# frankShield.net
KiCad netlist of a schematic drawn in EAGLE
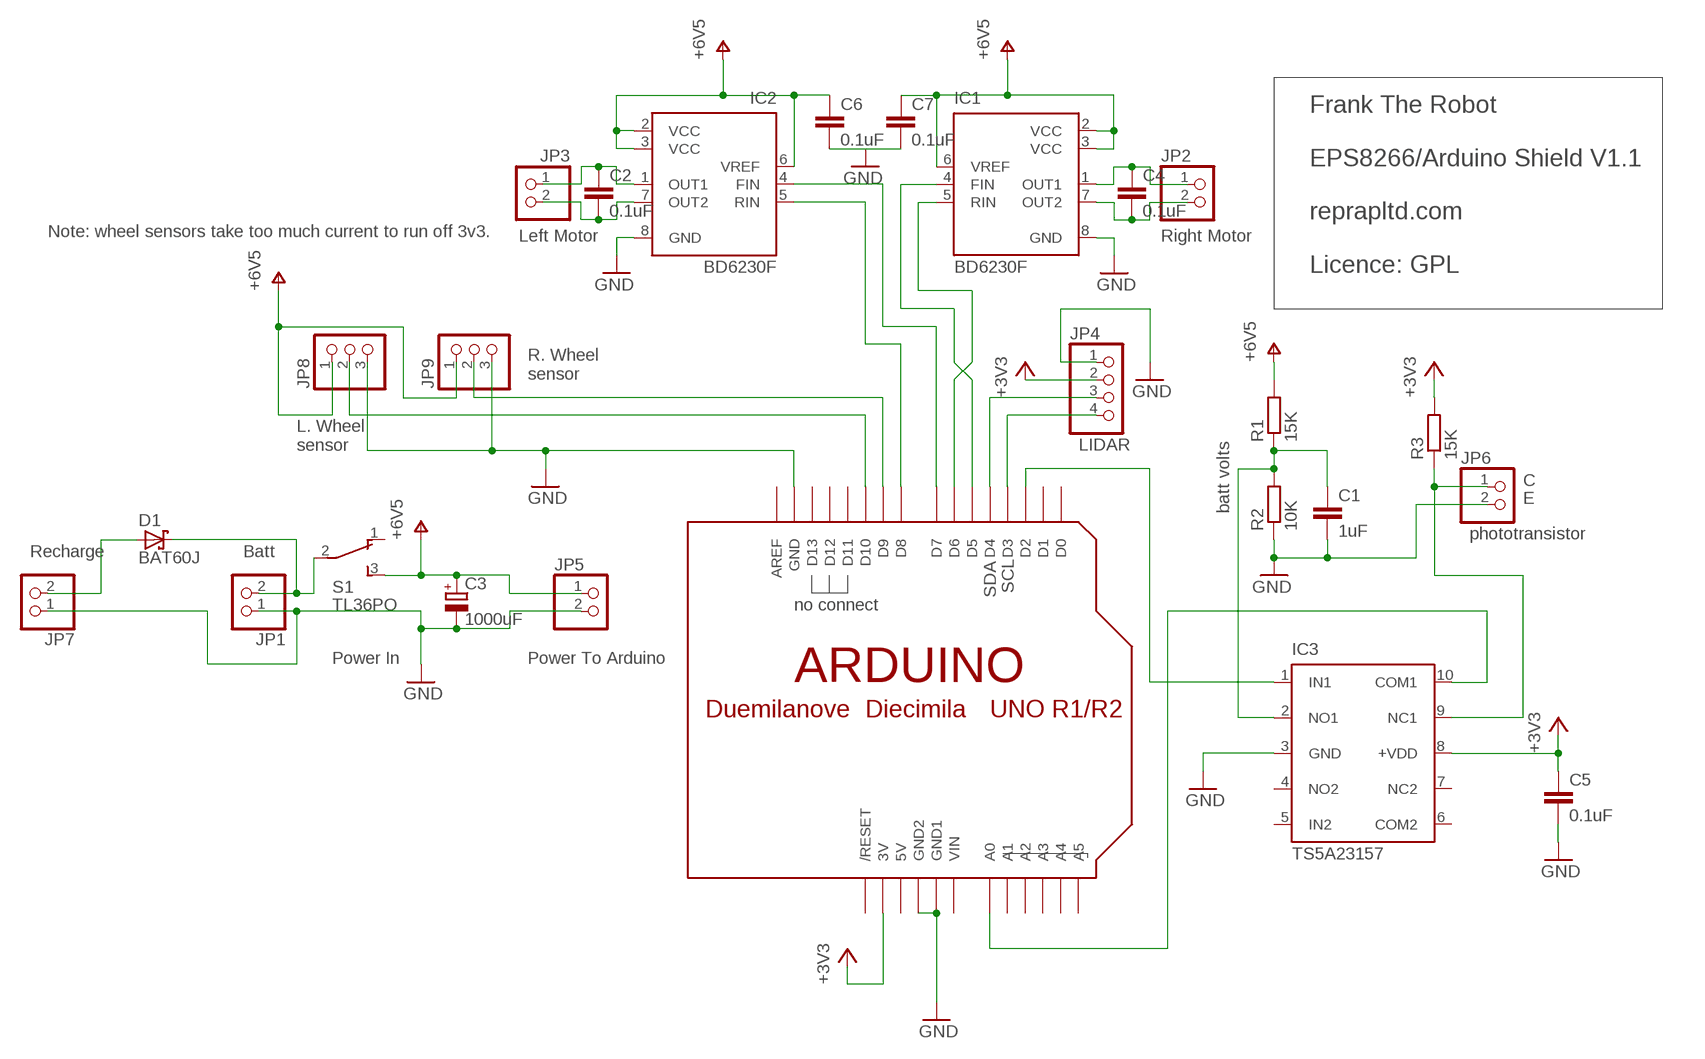
[diagram p0: schematic, sheet 1]

(export (version "E")
  (design (tool "Eeschema 10.0.6"))
  (components
    (comp (ref "C1")
      (value "1uF")
      (footprint "eagle-import:C0805")
      (libsource (lib "eagle-import") (part "C-EUC0805"))
    )
    (comp (ref "C2")
      (value "0.1uF")
      (footprint "eagle-import:C0805")
      (libsource (lib "eagle-import") (part "C-EUC0805"))
    )
    (comp (ref "C3")
      (value "1000uF")
      (footprint "eagle-import:B45181B")
      (libsource (lib "eagle-import") (part "CPOL-EUB45181B"))
    )
    (comp (ref "C4")
      (value "0.1uF")
      (footprint "eagle-import:C0805")
      (libsource (lib "eagle-import") (part "C-EUC0805"))
    )
    (comp (ref "C5")
      (value "0.1uF")
      (footprint "eagle-import:C0805")
      (libsource (lib "eagle-import") (part "C-EUC0805"))
    )
    (comp (ref "C6")
      (value "0.1uF")
      (footprint "eagle-import:C0805")
      (libsource (lib "eagle-import") (part "C-EUC0805"))
    )
    (comp (ref "C7")
      (value "0.1uF")
      (footprint "eagle-import:C0805")
      (libsource (lib "eagle-import") (part "C-EUC0805"))
    )
    (comp (ref "D1")
      (value "BAT60J")
      (footprint "eagle-import:SOD323_ST")
      (libsource (lib "eagle-import") (part "BAT60J"))
    )
    (comp (ref "IC1")
      (value "BD6230F")
      (footprint "eagle-import:SOP8")
      (fields (field (name "MPN") "BD6230F-E2"))
      (libsource (lib "eagle-import") (part "BD623F0"))
    )
    (comp (ref "IC2")
      (value "BD6230F")
      (footprint "eagle-import:SOP8")
      (fields (field (name "MPN") "BD6230F-E2"))
      (libsource (lib "eagle-import") (part "BD623F0"))
    )
    (comp (ref "IC3")
      (value "TS5A23157")
      (footprint "eagle-import:MSOP10")
      (fields (field (name "MPN") "AD7992BRMZ-0"))
      (libsource (lib "eagle-import") (part "TS5A23157"))
    )
    (comp (ref "JP1")
      (value "PINHD-1X2")
      (footprint "eagle-import:1X02")
      (libsource (lib "eagle-import") (part "PINHD-1X2"))
    )
    (comp (ref "JP2")
      (value "PINHD-1X2")
      (footprint "eagle-import:1X02")
      (libsource (lib "eagle-import") (part "PINHD-1X2"))
    )
    (comp (ref "JP3")
      (value "PINHD-1X2")
      (footprint "eagle-import:1X02")
      (libsource (lib "eagle-import") (part "PINHD-1X2"))
    )
    (comp (ref "JP4")
      (value "PINHD-1X4")
      (footprint "eagle-import:1X04")
      (libsource (lib "eagle-import") (part "PINHD-1X4"))
    )
    (comp (ref "JP5")
      (value "PINHD-1X2")
      (footprint "eagle-import:1X02")
      (libsource (lib "eagle-import") (part "PINHD-1X2"))
    )
    (comp (ref "JP6")
      (value "PINHD-1X2")
      (footprint "eagle-import:1X02")
      (libsource (lib "eagle-import") (part "PINHD-1X2"))
    )
    (comp (ref "JP7")
      (value "PINHD-1X2")
      (footprint "eagle-import:1X02")
      (libsource (lib "eagle-import") (part "PINHD-1X2"))
    )
    (comp (ref "JP8")
      (value "PINHD-1X3")
      (footprint "eagle-import:1X03")
      (libsource (lib "eagle-import") (part "PINHD-1X3"))
    )
    (comp (ref "JP9")
      (value "PINHD-1X3")
      (footprint "eagle-import:1X03")
      (libsource (lib "eagle-import") (part "PINHD-1X3"))
    )
    (comp (ref "R1")
      (value "15K")
      (footprint "eagle-import:M0805")
      (libsource (lib "eagle-import") (part "R-EU_M0805"))
    )
    (comp (ref "R2")
      (value "10K")
      (footprint "eagle-import:M0805")
      (libsource (lib "eagle-import") (part "R-EU_M0805"))
    )
    (comp (ref "R3")
      (value "15K")
      (footprint "eagle-import:M0805")
      (libsource (lib "eagle-import") (part "R-EU_M0805"))
    )
    (comp (ref "S1")
      (value "TL36PO")
      (footprint "eagle-import:TL3XPO")
      (libsource (lib "eagle-import") (part "TL36PO"))
    )
    (comp (ref "U$1")
      (value "ARDUINO-BPLACE")
      (footprint "eagle-import:ARDUINO-BPLACE")
      (libsource (lib "eagle-import") (part "ARDUINO-BPLACE"))
    )
  )
  (nets
    (net (code "1") (name "+3V3") (class "Default")
      (node (ref "C5") (pin "1") (pinfunction "1_1") (pintype "passive"))
      (node (ref "IC3") (pin "8") (pinfunction "+VDD_8") (pintype "output"))
      (node (ref "JP4") (pin "2") (pinfunction "2_2") (pintype "passive"))
      (node (ref "R3") (pin "2") (pinfunction "2_2") (pintype "passive"))
      (node (ref "U$1") (pin "3V") (pinfunction "3V_3V") (pintype "power_in"))
    )
    (net (code "2") (name "+6V5") (class "Default")
      (node (ref "C3") (pin "+") (pinfunction "+_+") (pintype "passive"))
      (node (ref "C6") (pin "1") (pinfunction "1_1") (pintype "passive"))
      (node (ref "C7") (pin "1") (pinfunction "1_1") (pintype "passive"))
      (node (ref "IC1") (pin "2") (pinfunction "VCC_2") (pintype "power_in"))
      (node (ref "IC1") (pin "3") (pinfunction "VCC_3") (pintype "power_in"))
      (node (ref "IC1") (pin "6") (pinfunction "VREF_6") (pintype "passive"))
      (node (ref "IC2") (pin "2") (pinfunction "VCC_2") (pintype "power_in"))
      (node (ref "IC2") (pin "3") (pinfunction "VCC_3") (pintype "power_in"))
      (node (ref "IC2") (pin "6") (pinfunction "VREF_6") (pintype "passive"))
      (node (ref "JP5") (pin "1") (pinfunction "1_1") (pintype "passive"))
      (node (ref "JP8") (pin "1") (pinfunction "1_1") (pintype "passive"))
      (node (ref "JP9") (pin "1") (pinfunction "1_1") (pintype "passive"))
      (node (ref "R1") (pin "2") (pinfunction "2_2") (pintype "passive"))
      (node (ref "S1") (pin "3") (pinfunction "S_3") (pintype "passive"))
    )
    (net (code "3") (name "/5V") (class "Default")
      (node (ref "U$1") (pin "5V") (pinfunction "5V_5V") (pintype "power_in"))
    )
    (net (code "4") (name "/NC2") (class "Default")
      (node (ref "IC3") (pin "7") (pinfunction "NC2_7") (pintype "power_in"))
    )
    (net (code "5") (name "/VIN") (class "Default")
      (node (ref "U$1") (pin "VIN") (pinfunction "VIN_VIN") (pintype "power_in"))
    )
    (net (code "6") (name "GND") (class "Default")
      (node (ref "C1") (pin "2") (pinfunction "2_2") (pintype "passive"))
      (node (ref "C3") (pin "-") (pinfunction "-_-") (pintype "passive"))
      (node (ref "C5") (pin "2") (pinfunction "2_2") (pintype "passive"))
      (node (ref "C6") (pin "2") (pinfunction "2_2") (pintype "passive"))
      (node (ref "C7") (pin "2") (pinfunction "2_2") (pintype "passive"))
      (node (ref "IC1") (pin "8") (pinfunction "GND_8") (pintype "power_in"))
      (node (ref "IC2") (pin "8") (pinfunction "GND_8") (pintype "power_in"))
      (node (ref "IC3") (pin "3") (pinfunction "GND_3") (pintype "power_in"))
      (node (ref "JP1") (pin "1") (pinfunction "1_1") (pintype "passive"))
      (node (ref "JP4") (pin "1") (pinfunction "1_1") (pintype "passive"))
      (node (ref "JP5") (pin "2") (pinfunction "2_2") (pintype "passive"))
      (node (ref "JP6") (pin "2") (pinfunction "2_2") (pintype "passive"))
      (node (ref "JP7") (pin "1") (pinfunction "1_1") (pintype "passive"))
      (node (ref "JP8") (pin "3") (pinfunction "3_3") (pintype "passive"))
      (node (ref "JP9") (pin "3") (pinfunction "3_3") (pintype "passive"))
      (node (ref "R2") (pin "1") (pinfunction "1_1") (pintype "passive"))
      (node (ref "U$1") (pin "GND") (pinfunction "GND_GND") (pintype "power_in"))
      (node (ref "U$1") (pin "GND1") (pinfunction "GND1_GND1") (pintype "power_in"))
      (node (ref "U$1") (pin "GND2") (pinfunction "GND2_GND2") (pintype "power_in"))
    )
    (net (code "7") (name "Net-(D1-PadA)") (class "Default")
      (node (ref "D1") (pin "A") (pinfunction "A_A") (pintype "passive"))
      (node (ref "JP7") (pin "2") (pinfunction "2_2") (pintype "passive"))
    )
    (net (code "8") (name "Net-(IC1-FIN)") (class "Default")
      (node (ref "IC1") (pin "4") (pinfunction "FIN_4") (pintype "input"))
      (node (ref "U$1") (pin "D5") (pinfunction "D5_D5") (pintype "bidirectional"))
    )
    (net (code "9") (name "Net-(IC1-OUT1)") (class "Default")
      (node (ref "C4") (pin "1") (pinfunction "1_1") (pintype "passive"))
      (node (ref "IC1") (pin "1") (pinfunction "OUT1_1") (pintype "output"))
      (node (ref "JP2") (pin "1") (pinfunction "1_1") (pintype "passive"))
    )
    (net (code "10") (name "Net-(IC1-OUT2)") (class "Default")
      (node (ref "C4") (pin "2") (pinfunction "2_2") (pintype "passive"))
      (node (ref "IC1") (pin "7") (pinfunction "OUT2_7") (pintype "output"))
      (node (ref "JP2") (pin "2") (pinfunction "2_2") (pintype "passive"))
    )
    (net (code "11") (name "Net-(IC1-RIN)") (class "Default")
      (node (ref "IC1") (pin "5") (pinfunction "RIN_5") (pintype "input"))
      (node (ref "U$1") (pin "D6") (pinfunction "D6_D6") (pintype "bidirectional"))
    )
    (net (code "12") (name "Net-(IC2-FIN)") (class "Default")
      (node (ref "IC2") (pin "4") (pinfunction "FIN_4") (pintype "input"))
      (node (ref "U$1") (pin "D7") (pinfunction "D7_D7") (pintype "bidirectional"))
    )
    (net (code "13") (name "Net-(IC2-OUT1)") (class "Default")
      (node (ref "C2") (pin "1") (pinfunction "1_1") (pintype "passive"))
      (node (ref "IC2") (pin "1") (pinfunction "OUT1_1") (pintype "output"))
      (node (ref "JP3") (pin "1") (pinfunction "1_1") (pintype "passive"))
    )
    (net (code "14") (name "Net-(IC2-OUT2)") (class "Default")
      (node (ref "C2") (pin "2") (pinfunction "2_2") (pintype "passive"))
      (node (ref "IC2") (pin "7") (pinfunction "OUT2_7") (pintype "output"))
      (node (ref "JP3") (pin "2") (pinfunction "2_2") (pintype "passive"))
    )
    (net (code "15") (name "Net-(IC2-RIN)") (class "Default")
      (node (ref "IC2") (pin "5") (pinfunction "RIN_5") (pintype "input"))
      (node (ref "U$1") (pin "D8") (pinfunction "D8_D8") (pintype "bidirectional"))
    )
    (net (code "16") (name "Net-(IC3-COM1)") (class "Default")
      (node (ref "IC3") (pin "10") (pinfunction "COM1_10") (pintype "input"))
      (node (ref "U$1") (pin "A0") (pinfunction "A0_A0") (pintype "bidirectional"))
    )
    (net (code "17") (name "Net-(IC3-IN1)") (class "Default")
      (node (ref "IC3") (pin "1") (pinfunction "IN1_1") (pintype "input"))
      (node (ref "U$1") (pin "D2") (pinfunction "D2_D2") (pintype "bidirectional"))
    )
    (net (code "18") (name "Net-(IC3-NC1)") (class "Default")
      (node (ref "IC3") (pin "9") (pinfunction "NC1_9") (pintype "bidirectional"))
      (node (ref "JP6") (pin "1") (pinfunction "1_1") (pintype "passive"))
      (node (ref "R3") (pin "1") (pinfunction "1_1") (pintype "passive"))
    )
    (net (code "19") (name "Net-(IC3-NO1)") (class "Default")
      (node (ref "C1") (pin "1") (pinfunction "1_1") (pintype "passive"))
      (node (ref "IC3") (pin "2") (pinfunction "NO1_2") (pintype "power_in"))
      (node (ref "R1") (pin "1") (pinfunction "1_1") (pintype "passive"))
      (node (ref "R2") (pin "2") (pinfunction "2_2") (pintype "passive"))
    )
    (net (code "20") (name "Net-(JP4-Pad3)") (class "Default")
      (node (ref "JP4") (pin "3") (pinfunction "3_3") (pintype "passive"))
      (node (ref "U$1") (pin "D4") (pinfunction "D4_D4") (pintype "bidirectional"))
    )
    (net (code "21") (name "Net-(JP4-Pad4)") (class "Default")
      (node (ref "JP4") (pin "4") (pinfunction "4_4") (pintype "passive"))
      (node (ref "U$1") (pin "D3") (pinfunction "D3_D3") (pintype "bidirectional"))
    )
    (net (code "22") (name "Net-(JP8-Pad2)") (class "Default")
      (node (ref "JP8") (pin "2") (pinfunction "2_2") (pintype "passive"))
      (node (ref "U$1") (pin "D10") (pinfunction "D10_D10") (pintype "bidirectional"))
    )
    (net (code "23") (name "Net-(JP9-Pad2)") (class "Default")
      (node (ref "JP9") (pin "2") (pinfunction "2_2") (pintype "passive"))
      (node (ref "U$1") (pin "D9") (pinfunction "D9_D9") (pintype "bidirectional"))
    )
    (net (code "24") (name "Net-(S1-P)") (class "Default")
      (node (ref "D1") (pin "C") (pinfunction "C_C") (pintype "passive"))
      (node (ref "JP1") (pin "2") (pinfunction "2_2") (pintype "passive"))
      (node (ref "S1") (pin "2") (pinfunction "P_2") (pintype "passive"))
    )
    (net (code "25") (name "unconnected-(IC3-COM2-Pad6)") (class "Default")
      (node (ref "IC3") (pin "6") (pinfunction "COM2_6") (pintype "input"))
    )
    (net (code "26") (name "unconnected-(IC3-IN2-Pad5)") (class "Default")
      (node (ref "IC3") (pin "5") (pinfunction "IN2_5") (pintype "input"))
    )
    (net (code "27") (name "unconnected-(IC3-NO2-Pad4)") (class "Default")
      (node (ref "IC3") (pin "4") (pinfunction "NO2_4") (pintype "input"))
    )
    (net (code "28") (name "unconnected-(S1-O-Pad1)") (class "Default")
      (node (ref "S1") (pin "1") (pinfunction "O_1") (pintype "passive"))
    )
    (net (code "29") (name "unconnected-(U$1-PadA1)") (class "Default")
      (node (ref "U$1") (pin "A1") (pinfunction "A1_A1") (pintype "bidirectional"))
    )
    (net (code "30") (name "unconnected-(U$1-PadA2)") (class "Default")
      (node (ref "U$1") (pin "A2") (pinfunction "A2_A2") (pintype "bidirectional"))
    )
    (net (code "31") (name "unconnected-(U$1-PadA3)") (class "Default")
      (node (ref "U$1") (pin "A3") (pinfunction "A3_A3") (pintype "bidirectional"))
    )
    (net (code "32") (name "unconnected-(U$1-PadA4)") (class "Default")
      (node (ref "U$1") (pin "A4") (pinfunction "A4_A4") (pintype "bidirectional"))
    )
    (net (code "33") (name "unconnected-(U$1-PadA5)") (class "Default")
      (node (ref "U$1") (pin "A5") (pinfunction "A5_A5") (pintype "bidirectional"))
    )
    (net (code "34") (name "unconnected-(U$1-PadAREF)") (class "Default")
      (node (ref "U$1") (pin "AREF") (pinfunction "AREF_AREF") (pintype "bidirectional"))
    )
    (net (code "35") (name "unconnected-(U$1-PadD0)") (class "Default")
      (node (ref "U$1") (pin "D0") (pinfunction "D0_D0") (pintype "bidirectional"))
    )
    (net (code "36") (name "unconnected-(U$1-PadD1)") (class "Default")
      (node (ref "U$1") (pin "D1") (pinfunction "D1_D1") (pintype "bidirectional"))
    )
    (net (code "37") (name "unconnected-(U$1-PadD11)") (class "Default")
      (node (ref "U$1") (pin "D11") (pinfunction "D11_D11") (pintype "bidirectional"))
    )
    (net (code "38") (name "unconnected-(U$1-PadD12)") (class "Default")
      (node (ref "U$1") (pin "D12") (pinfunction "D12_D12") (pintype "bidirectional"))
    )
    (net (code "39") (name "unconnected-(U$1-PadD13)") (class "Default")
      (node (ref "U$1") (pin "D13") (pinfunction "D13_D13") (pintype "bidirectional"))
    )
    (net (code "40") (name "unconnected-(U$1-{slash}RESET-PadRESET)") (class "Default")
      (node (ref "U$1") (pin "RESET") (pinfunction "/RESET_RESET") (pintype "bidirectional"))
    )
  )
)
